# meter_channel.net
KiCad netlist of a schematic drawn in Altium Designer
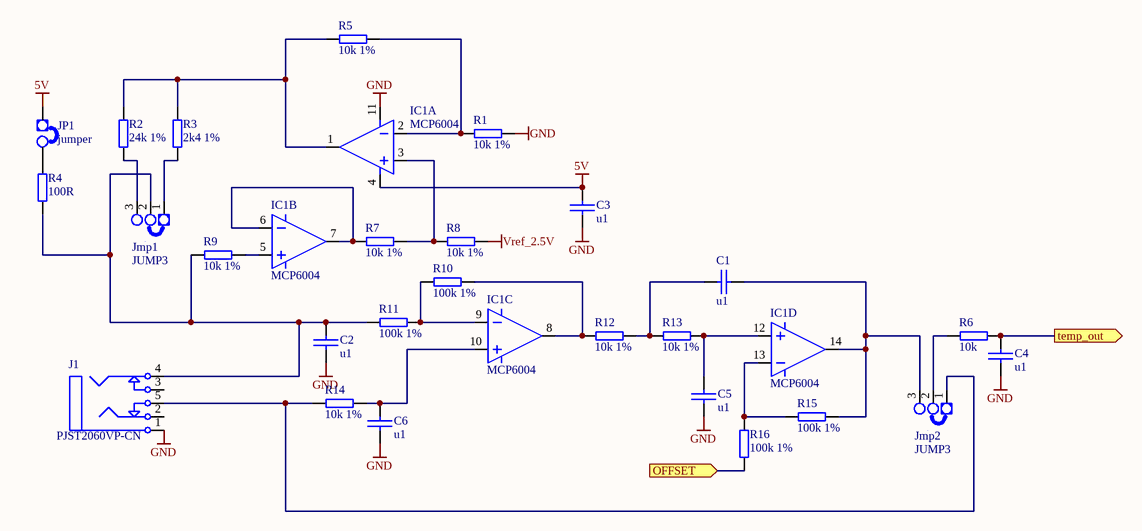
[diagram p0: meter_channel.SchDoc]

(export (version "E")
  (design (tool "Eeschema 10.0.6"))
  (components
    (comp (ref "C1")
      (value "u1")
      (footprint "0603C")
      (description "Capacitor SMD")
      (libsource (lib "LIBRARY_SCH") (part "CAP_SMD"))
    )
    (comp (ref "C2")
      (value "u1")
      (footprint "0603C")
      (description "Capacitor SMD")
      (libsource (lib "LIBRARY_SCH") (part "CAP_SMD"))
    )
    (comp (ref "C3")
      (value "u1")
      (footprint "0603C")
      (description "Capacitor SMD")
      (libsource (lib "LIBRARY_SCH") (part "CAP_SMD"))
    )
    (comp (ref "C4")
      (value "u1")
      (footprint "0603C")
      (description "Capacitor SMD")
      (libsource (lib "LIBRARY_SCH") (part "CAP_SMD"))
    )
    (comp (ref "C5")
      (value "u1")
      (footprint "0603C")
      (description "Capacitor SMD")
      (libsource (lib "LIBRARY_SCH") (part "CAP_SMD"))
    )
    (comp (ref "C6")
      (value "u1")
      (footprint "0603C")
      (description "Capacitor SMD")
      (libsource (lib "LIBRARY_SCH") (part "CAP_SMD"))
    )
    (comp (ref "IC1")
      (value "MCP6004")
      (footprint "TSSOP14-4.4")
      (description "micropower opamp")
      (libsource (lib "LIBRARY_SCH") (part "OA_MCP6004"))
    )
    (comp (ref "J1")
      (value "PJST2060VP-CN")
      (footprint "ST-3150-5N")
      (description "3-Conductor Jack with 2 break contacts (normals) and 2 auxiliary make contacts")
      (fields (field (name "PUBLISHER") "Altium Limited"))
      (libsource (lib "LIBRARY_SCH") (part "CON_Phonejack Stereo SW"))
    )
    (comp (ref "Jmp1") (value "JUMP3") (footprint "jump3") (libsource (lib "LIBRARY_SCH") (part "JUMP3")))
    (comp (ref "Jmp2") (value "JUMP3") (footprint "jump3") (libsource (lib "LIBRARY_SCH") (part "JUMP3")))
    (comp (ref "JP1")
      (value "jumper")
      (footprint "jump")
      (description "Jumper")
      (libsource (lib "LIBRARY_SCH") (part "JUMPER"))
    )
    (comp (ref "R1")
      (value "10k 1%")
      (footprint "0603R")
      (description "Resistor")
      (libsource (lib "LIBRARY_SCH") (part "RES2"))
    )
    (comp (ref "R2")
      (value "24k 1%")
      (footprint "0603R")
      (description "Resistor")
      (libsource (lib "LIBRARY_SCH") (part "RES2"))
    )
    (comp (ref "R3")
      (value "2k4 1%")
      (footprint "0603R")
      (description "Resistor")
      (libsource (lib "LIBRARY_SCH") (part "RES2"))
    )
    (comp (ref "R4")
      (value "100R")
      (footprint "0603R")
      (description "Resistor")
      (libsource (lib "LIBRARY_SCH") (part "RES2"))
    )
    (comp (ref "R5")
      (value "10k 1%")
      (footprint "0603R")
      (description "Resistor")
      (libsource (lib "LIBRARY_SCH") (part "RES2"))
    )
    (comp (ref "R6")
      (value "10k")
      (footprint "0603R")
      (description "Resistor")
      (libsource (lib "LIBRARY_SCH") (part "RES2"))
    )
    (comp (ref "R7")
      (value "10k 1%")
      (footprint "0603R")
      (description "Resistor")
      (libsource (lib "LIBRARY_SCH") (part "RES2"))
    )
    (comp (ref "R8")
      (value "10k 1%")
      (footprint "0603R")
      (description "Resistor")
      (libsource (lib "LIBRARY_SCH") (part "RES2"))
    )
    (comp (ref "R9")
      (value "10k 1%")
      (footprint "0603R")
      (description "Resistor")
      (libsource (lib "LIBRARY_SCH") (part "RES2"))
    )
    (comp (ref "R10")
      (value "100k 1%")
      (footprint "0603R")
      (description "Resistor")
      (libsource (lib "LIBRARY_SCH") (part "RES2"))
    )
    (comp (ref "R11")
      (value "100k 1%")
      (footprint "0603R")
      (description "Resistor")
      (libsource (lib "LIBRARY_SCH") (part "RES2"))
    )
    (comp (ref "R12")
      (value "10k 1%")
      (footprint "0603R")
      (description "Resistor")
      (libsource (lib "LIBRARY_SCH") (part "RES2"))
    )
    (comp (ref "R13")
      (value "10k 1%")
      (footprint "0603R")
      (description "Resistor")
      (libsource (lib "LIBRARY_SCH") (part "RES2"))
    )
    (comp (ref "R14")
      (value "10k 1%")
      (footprint "0603R")
      (description "Resistor")
      (libsource (lib "LIBRARY_SCH") (part "RES2"))
    )
    (comp (ref "R15")
      (value "100k 1%")
      (footprint "0603R")
      (description "Resistor")
      (libsource (lib "LIBRARY_SCH") (part "RES2"))
    )
    (comp (ref "R16")
      (value "100k 1%")
      (footprint "0603R")
      (description "Resistor")
      (libsource (lib "LIBRARY_SCH") (part "RES2"))
    )
  )
  (nets
    (net (code "1") (name "/OFFSET") (class "Default")
      (node (ref "R16") (pin "1") (pinfunction "1_1") (pintype "passive"))
    )
    (net (code "2") (name "/temp_out") (class "Default")
      (node (ref "C4") (pin "2") (pinfunction "2_2") (pintype "passive"))
      (node (ref "R6") (pin "1") (pinfunction "1_1") (pintype "passive"))
    )
    (net (code "3") (name "5V") (class "Default")
      (node (ref "C3") (pin "1") (pinfunction "1_1") (pintype "passive"))
      (node (ref "IC1") (pin "4") (pintype "passive"))
      (node (ref "JP1") (pin "1") (pinfunction "E1_1") (pintype "passive"))
    )
    (net (code "4") (name "GND") (class "Default")
      (node (ref "C2") (pin "2") (pinfunction "2_2") (pintype "passive"))
      (node (ref "C3") (pin "2") (pinfunction "2_2") (pintype "passive"))
      (node (ref "C4") (pin "1") (pinfunction "1_1") (pintype "passive"))
      (node (ref "C5") (pin "1") (pinfunction "1_1") (pintype "passive"))
      (node (ref "C6") (pin "2") (pinfunction "2_2") (pintype "passive"))
      (node (ref "IC1") (pin "11") (pintype "passive"))
      (node (ref "J1") (pin "1") (pintype "passive"))
      (node (ref "R1") (pin "1") (pinfunction "1_1") (pintype "passive"))
    )
    (net (code "5") (name "Net-(C1-Pad1)") (class "Default")
      (node (ref "C1") (pin "1") (pinfunction "1_1") (pintype "passive"))
      (node (ref "R12") (pin "2") (pinfunction "2_2") (pintype "passive"))
      (node (ref "R13") (pin "1") (pinfunction "1_1") (pintype "passive"))
    )
    (net (code "6") (name "Net-(C1-Pad2)") (class "Default")
      (node (ref "C1") (pin "2") (pinfunction "2_2") (pintype "passive"))
      (node (ref "IC1") (pin "14") (pintype "passive"))
      (node (ref "Jmp2") (pin "3") (pintype "passive"))
      (node (ref "R15") (pin "2") (pinfunction "2_2") (pintype "passive"))
    )
    (net (code "7") (name "Net-(C2-Pad1)") (class "Default")
      (node (ref "C2") (pin "1") (pinfunction "1_1") (pintype "passive"))
      (node (ref "J1") (pin "4") (pintype "passive"))
      (node (ref "Jmp1") (pin "2") (pintype "passive"))
      (node (ref "R11") (pin "1") (pinfunction "1_1") (pintype "passive"))
      (node (ref "R4") (pin "2") (pinfunction "2_2") (pintype "passive"))
      (node (ref "R9") (pin "1") (pinfunction "1_1") (pintype "passive"))
    )
    (net (code "8") (name "Net-(C5-Pad2)") (class "Default")
      (node (ref "C5") (pin "2") (pinfunction "2_2") (pintype "passive"))
      (node (ref "IC1") (pin "12") (pintype "passive"))
      (node (ref "R13") (pin "2") (pinfunction "2_2") (pintype "passive"))
    )
    (net (code "9") (name "Net-(C6-Pad1)") (class "Default")
      (node (ref "C6") (pin "1") (pinfunction "1_1") (pintype "passive"))
      (node (ref "IC1") (pin "10") (pintype "passive"))
      (node (ref "R14") (pin "2") (pinfunction "2_2") (pintype "passive"))
    )
    (net (code "10") (name "Net-(IC1-Pad1)") (class "Default")
      (node (ref "IC1") (pin "1") (pintype "passive"))
      (node (ref "R2") (pin "1") (pinfunction "1_1") (pintype "passive"))
      (node (ref "R3") (pin "1") (pinfunction "1_1") (pintype "passive"))
      (node (ref "R5") (pin "2") (pinfunction "2_2") (pintype "passive"))
    )
    (net (code "11") (name "Net-(IC1-Pad2)") (class "Default")
      (node (ref "IC1") (pin "2") (pintype "passive"))
      (node (ref "R1") (pin "2") (pinfunction "2_2") (pintype "passive"))
      (node (ref "R5") (pin "1") (pinfunction "1_1") (pintype "passive"))
    )
    (net (code "12") (name "Net-(IC1-Pad3)") (class "Default")
      (node (ref "IC1") (pin "3") (pintype "passive"))
      (node (ref "R7") (pin "2") (pinfunction "2_2") (pintype "passive"))
      (node (ref "R8") (pin "1") (pinfunction "1_1") (pintype "passive"))
    )
    (net (code "13") (name "Net-(IC1-Pad5)") (class "Default")
      (node (ref "IC1") (pin "5") (pintype "passive"))
      (node (ref "R9") (pin "2") (pinfunction "2_2") (pintype "passive"))
    )
    (net (code "14") (name "Net-(IC1-Pad6)") (class "Default")
      (node (ref "IC1") (pin "6") (pintype "passive"))
      (node (ref "IC1") (pin "7") (pintype "passive"))
      (node (ref "R7") (pin "1") (pinfunction "1_1") (pintype "passive"))
    )
    (net (code "15") (name "Net-(IC1-Pad8)") (class "Default")
      (node (ref "IC1") (pin "8") (pintype "passive"))
      (node (ref "R10") (pin "2") (pinfunction "2_2") (pintype "passive"))
      (node (ref "R12") (pin "1") (pinfunction "1_1") (pintype "passive"))
    )
    (net (code "16") (name "Net-(IC1-Pad9)") (class "Default")
      (node (ref "IC1") (pin "9") (pintype "passive"))
      (node (ref "R10") (pin "1") (pinfunction "1_1") (pintype "passive"))
      (node (ref "R11") (pin "2") (pinfunction "2_2") (pintype "passive"))
    )
    (net (code "17") (name "Net-(IC1-Pad13)") (class "Default")
      (node (ref "IC1") (pin "13") (pintype "passive"))
      (node (ref "R15") (pin "1") (pinfunction "1_1") (pintype "passive"))
      (node (ref "R16") (pin "2") (pinfunction "2_2") (pintype "passive"))
    )
    (net (code "18") (name "Net-(J1-Pad5)") (class "Default")
      (node (ref "J1") (pin "5") (pintype "passive"))
      (node (ref "Jmp2") (pin "1") (pintype "passive"))
      (node (ref "R14") (pin "1") (pinfunction "1_1") (pintype "passive"))
    )
    (net (code "19") (name "Net-(JP1-E2)") (class "Default")
      (node (ref "JP1") (pin "2") (pinfunction "E2_2") (pintype "passive"))
      (node (ref "R4") (pin "1") (pinfunction "1_1") (pintype "passive"))
    )
    (net (code "20") (name "Net-(Jmp1-Pad1)") (class "Default")
      (node (ref "Jmp1") (pin "1") (pintype "passive"))
      (node (ref "R3") (pin "2") (pinfunction "2_2") (pintype "passive"))
    )
    (net (code "21") (name "Net-(Jmp1-Pad3)") (class "Default")
      (node (ref "Jmp1") (pin "3") (pintype "passive"))
      (node (ref "R2") (pin "2") (pinfunction "2_2") (pintype "passive"))
    )
    (net (code "22") (name "Net-(Jmp2-Pad2)") (class "Default")
      (node (ref "Jmp2") (pin "2") (pintype "passive"))
      (node (ref "R6") (pin "2") (pinfunction "2_2") (pintype "passive"))
    )
    (net (code "23") (name "Vref_2.5V") (class "Default")
      (node (ref "R8") (pin "2") (pinfunction "2_2") (pintype "passive"))
    )
    (net (code "24") (name "unconnected-(J1-Pad2)") (class "Default")
      (node (ref "J1") (pin "2") (pintype "passive"))
    )
    (net (code "25") (name "unconnected-(J1-Pad3)") (class "Default")
      (node (ref "J1") (pin "3") (pintype "passive"))
    )
  )
)
